# TopSheet.net
KiCad netlist of a schematic drawn in Altium Designer
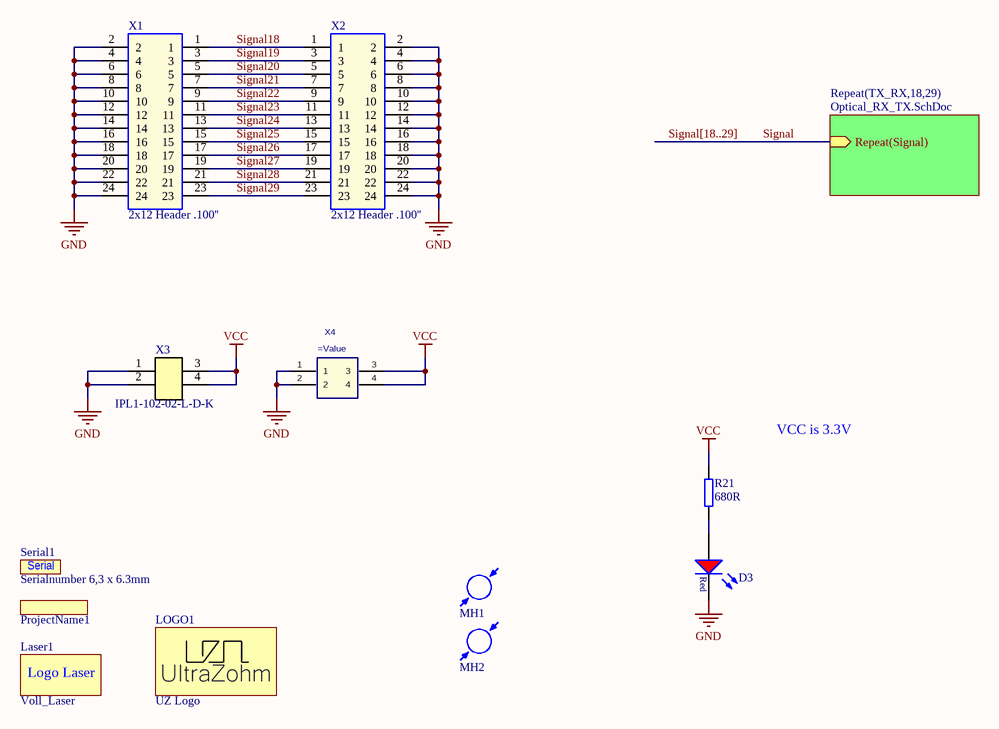
[diagram p0: TopSheet.SchDoc]

(export (version "E")
  (design (tool "Eeschema 10.0.6"))
  (components
    (comp (ref "D3")
      (value "150060RS75000")
      (footprint "WL-SMCW_0603")
      (description "WL-SMCW SMD Mono-color Chip LED Waterclear, size 0603, Red, 2 V, 140°")
      (fields
        (field (name "MF") "Wuerth Elektronik")
        (field (name "LCSC PART NUMBER") "C2286")
        (field (name "CREATED") "2018_09_06_AGeiger")
      )
      (libsource (lib "UZOhm_Optical") (part "LED_Red_0603"))
    )
    (comp (ref "Laser1")
      (value "Voll_Laser")
      (footprint "Voll_Laser")
      (description "Logo Laser Warning Sign")
      (libsource (lib "UZOhm_Optical") (part "Voll_Laser"))
    )
    (comp (ref "LOGO1")
      (value "UZ Logo")
      (footprint "UZ_Logo_small")
      (description "UltraZohm Logo on PCB")
      (fields (field (name "CREATED") "Jan2021_Liegmann"))
      (libsource (lib "PCB_Logo") (part "UZ Logo"))
    )
    (comp (ref "MH1")
      (value "MH_2.8")
      (footprint "MH_2.8")
      (description "Non plated through hole")
      (libsource (lib "UZOhm_Optical") (part "Mounting Hole"))
    )
    (comp (ref "MH2")
      (value "MH_2.8")
      (footprint "MH_2.8")
      (description "Non plated through hole")
      (libsource (lib "UZOhm_Optical") (part "Mounting Hole"))
    )
    (comp (ref "ProjectName1")
      (value "Project Name, Rev")
      (footprint "ID_ProjectRev")
      (description "Project Name and Revision Number")
      (fields (field (name "CREATED") "2018_11_23_AGeiger"))
      (libsource (lib "UZOhm_Optical") (part "ID_ProjectRev"))
    )
    (comp (ref "R21")
      (value "680R")
      (footprint "R_0603_N")
      (description "SMD Resistor 0603")
      (fields
        (field (name "TOLERANCE") "1%")
        (field (name "VOLTAGE") "75V")
        (field (name "CREATED") "2018_09_06_AGeiger")
      )
      (libsource (lib "UZOhm_Optical") (part "R_0603"))
    )
    (comp (ref "Serial1")
      (value "Serialnumber 6,3 x 6.3mm")
      (footprint "Serial_6.3x6.3mm")
      (fields (field (name "CREATED") "2018_09_18_AGeiger"))
      (libsource (lib "UZOhm_Optical") (part "SerialNumber"))
    )
    (comp (ref "X1")
      (value "2x12 Header .100''")
      (footprint "TST-112-01-G-D")
      (description "Double Row, 12 positions, Shrouded Terminal Header .100''")
      (fields
        (field (name "MF") "Samtec")
        (field (name "MPN") "TST-112-01-G-D")
        (field (name "CREATED") "2020_04_Kreppel")
      )
      (libsource (lib "UZOhm_Optical") (part "TST-112-01-G-D"))
    )
    (comp (ref "X2")
      (value "2x12 Header .100''")
      (footprint "TST-112-01-G-D")
      (description "Double Row, 12 positions, Shrouded Terminal Header .100''")
      (fields
        (field (name "MF") "Samtec")
        (field (name "MPN") "TST-112-01-G-D")
        (field (name "CREATED") "2020_04_Kreppel")
      )
      (libsource (lib "") (part "TST-112-01-G-D_1"))
    )
    (comp (ref "X3")
      (value "IPL1-102-02-L-D-K")
      (footprint "IPL1-102-02-L-D-K-0")
      (description "P=2.54mm Wire To Board Connector ROHS")
      (fields
        (field (name "MANUFACTURER") "SAMTEC")
        (field (name "LCSC PART NUMBER") "C7437440")
        (field (name "CREATED FROM") "KIlhan")
      )
      (libsource (lib "user") (part "IPL1-102-02-L-D-K"))
    )
    (comp (ref "X4")
      (value "~")
      (footprint "IPL1-102-01-L-D-K")
      (description "2.54mm Double Row Terminal Assembly, Right-Angled")
      (fields
        (field (name "MANUFACTURER") "SAMTEC")
        (field (name "LCSC PART NUMBER") "C5714565")
        (field (name "CREATED") "2018_05_02_AGeiger")
      )
      (libsource (lib "UZOhm_Optical") (part "IPL1-102-XX-X-D-X"))
    )
  )
  (nets
    (net (code "2") (name "/Signal18") (class "Default")
      (node (ref "X1") (pin "1") (pinfunction "1_1") (pintype "passive"))
      (node (ref "X2") (pin "1") (pinfunction "1_1") (pintype "passive"))
    )
    (net (code "3") (name "/Signal19") (class "Default")
      (node (ref "X1") (pin "3") (pinfunction "3_3") (pintype "passive"))
      (node (ref "X2") (pin "3") (pinfunction "3_3") (pintype "passive"))
    )
    (net (code "4") (name "/Signal20") (class "Default")
      (node (ref "X1") (pin "5") (pinfunction "5_5") (pintype "passive"))
      (node (ref "X2") (pin "5") (pinfunction "5_5") (pintype "passive"))
    )
    (net (code "5") (name "/Signal21") (class "Default")
      (node (ref "X1") (pin "7") (pinfunction "7_7") (pintype "passive"))
      (node (ref "X2") (pin "7") (pinfunction "7_7") (pintype "passive"))
    )
    (net (code "6") (name "/Signal22") (class "Default")
      (node (ref "X1") (pin "9") (pinfunction "9_9") (pintype "passive"))
      (node (ref "X2") (pin "9") (pinfunction "9_9") (pintype "passive"))
    )
    (net (code "7") (name "/Signal23") (class "Default")
      (node (ref "X1") (pin "11") (pinfunction "11_11") (pintype "passive"))
      (node (ref "X2") (pin "11") (pinfunction "11_11") (pintype "passive"))
    )
    (net (code "8") (name "/Signal24") (class "Default")
      (node (ref "X1") (pin "13") (pinfunction "13_13") (pintype "passive"))
      (node (ref "X2") (pin "13") (pinfunction "13_13") (pintype "passive"))
    )
    (net (code "9") (name "/Signal25") (class "Default")
      (node (ref "X1") (pin "15") (pinfunction "15_15") (pintype "passive"))
      (node (ref "X2") (pin "15") (pinfunction "15_15") (pintype "passive"))
    )
    (net (code "10") (name "/Signal26") (class "Default")
      (node (ref "X1") (pin "17") (pinfunction "17_17") (pintype "passive"))
      (node (ref "X2") (pin "17") (pinfunction "17_17") (pintype "passive"))
    )
    (net (code "11") (name "/Signal27") (class "Default")
      (node (ref "X1") (pin "19") (pinfunction "19_19") (pintype "passive"))
      (node (ref "X2") (pin "19") (pinfunction "19_19") (pintype "passive"))
    )
    (net (code "12") (name "/Signal28") (class "Default")
      (node (ref "X1") (pin "21") (pinfunction "21_21") (pintype "passive"))
      (node (ref "X2") (pin "21") (pinfunction "21_21") (pintype "passive"))
    )
    (net (code "13") (name "/Signal29") (class "Default")
      (node (ref "X1") (pin "23") (pinfunction "23_23") (pintype "passive"))
      (node (ref "X2") (pin "23") (pinfunction "23_23") (pintype "passive"))
    )
    (net (code "15") (name "GND") (class "Default")
      (node (ref "D3") (pin "1") (pinfunction "K_1") (pintype "passive"))
      (node (ref "X1") (pin "10") (pinfunction "10_10") (pintype "passive"))
      (node (ref "X1") (pin "12") (pinfunction "12_12") (pintype "passive"))
      (node (ref "X1") (pin "14") (pinfunction "14_14") (pintype "passive"))
      (node (ref "X1") (pin "16") (pinfunction "16_16") (pintype "passive"))
      (node (ref "X1") (pin "18") (pinfunction "18_18") (pintype "passive"))
      (node (ref "X1") (pin "2") (pinfunction "2_2") (pintype "passive"))
      (node (ref "X1") (pin "20") (pinfunction "20_20") (pintype "passive"))
      (node (ref "X1") (pin "22") (pinfunction "22_22") (pintype "passive"))
      (node (ref "X1") (pin "24") (pinfunction "24_24") (pintype "passive"))
      (node (ref "X1") (pin "4") (pinfunction "4_4") (pintype "passive"))
      (node (ref "X1") (pin "6") (pinfunction "6_6") (pintype "passive"))
      (node (ref "X1") (pin "8") (pinfunction "8_8") (pintype "passive"))
      (node (ref "X2") (pin "10") (pinfunction "10_10") (pintype "passive"))
      (node (ref "X2") (pin "12") (pinfunction "12_12") (pintype "passive"))
      (node (ref "X2") (pin "14") (pinfunction "14_14") (pintype "passive"))
      (node (ref "X2") (pin "16") (pinfunction "16_16") (pintype "passive"))
      (node (ref "X2") (pin "18") (pinfunction "18_18") (pintype "passive"))
      (node (ref "X2") (pin "2") (pinfunction "2_2") (pintype "passive"))
      (node (ref "X2") (pin "20") (pinfunction "20_20") (pintype "passive"))
      (node (ref "X2") (pin "22") (pinfunction "22_22") (pintype "passive"))
      (node (ref "X2") (pin "24") (pinfunction "24_24") (pintype "passive"))
      (node (ref "X2") (pin "4") (pinfunction "4_4") (pintype "passive"))
      (node (ref "X2") (pin "6") (pinfunction "6_6") (pintype "passive"))
      (node (ref "X2") (pin "8") (pinfunction "8_8") (pintype "passive"))
      (node (ref "X3") (pin "1") (pinfunction "1_1") (pintype "passive"))
      (node (ref "X3") (pin "2") (pinfunction "2_2") (pintype "passive"))
      (node (ref "X4") (pin "1") (pinfunction "1_1") (pintype "passive"))
      (node (ref "X4") (pin "2") (pinfunction "2_2") (pintype "passive"))
    )
    (net (code "16") (name "Net-(D3-A)") (class "Default")
      (node (ref "D3") (pin "2") (pinfunction "A_2") (pintype "passive"))
      (node (ref "R21") (pin "1") (pinfunction "1_1") (pintype "passive"))
    )
    (net (code "17") (name "VCC") (class "Default")
      (node (ref "R21") (pin "2") (pinfunction "2_2") (pintype "passive"))
      (node (ref "X3") (pin "3") (pinfunction "3_3") (pintype "passive"))
      (node (ref "X3") (pin "4") (pinfunction "4_4") (pintype "passive"))
      (node (ref "X4") (pin "3") (pinfunction "3_3") (pintype "passive"))
      (node (ref "X4") (pin "4") (pinfunction "4_4") (pintype "passive"))
    )
  )
)
